# Sensors.net
KiCad netlist of a schematic drawn in Altium Designer
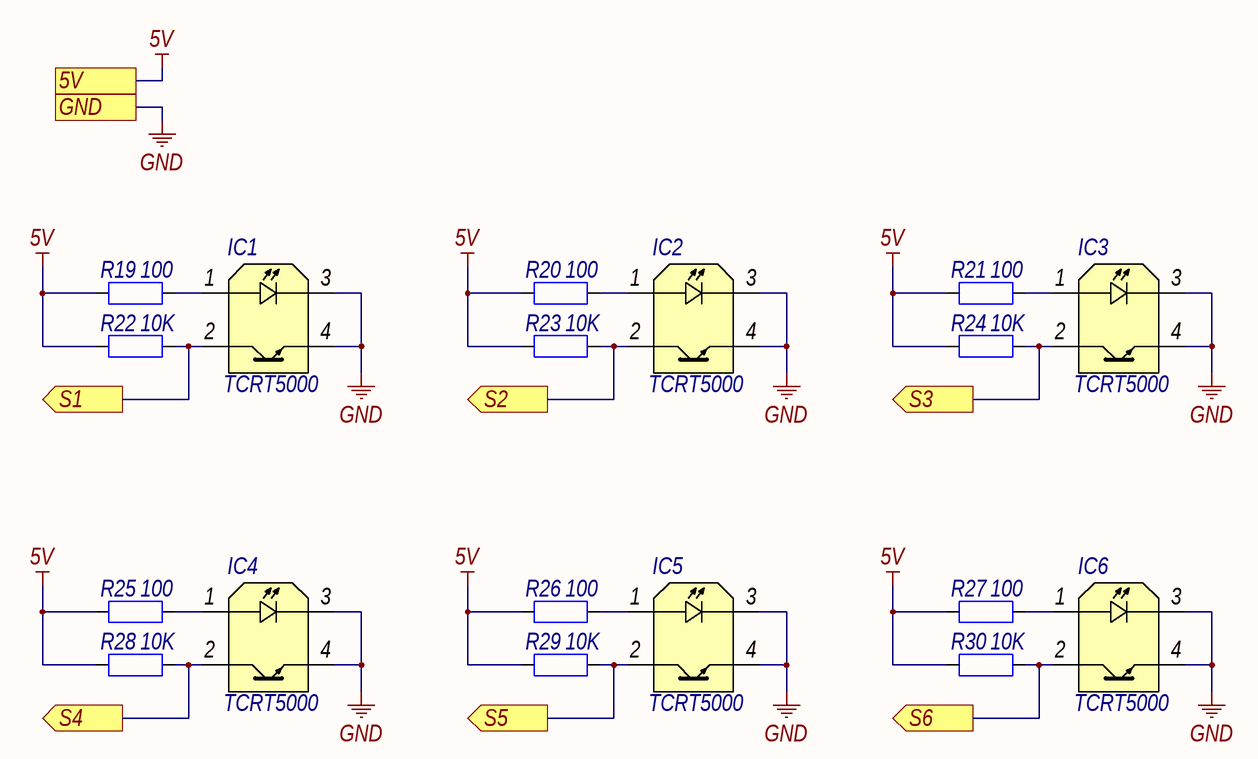
[diagram p0: Sensors.SchDoc]

(export (version "E")
  (design (tool "Eeschema 10.0.6"))
  (components
    (comp (ref "IC1")
      (value "TCRT5000")
      (footprint "Footprints:TCRT5000")
      (description "IR photointerrupter")
      (libsource (lib "Miscellaneous") (part "TCRT5000"))
    )
    (comp (ref "IC2")
      (value "TCRT5000")
      (footprint "Footprints:TCRT5000")
      (description "IR photointerrupter")
      (libsource (lib "Miscellaneous") (part "TCRT5000"))
    )
    (comp (ref "IC3")
      (value "TCRT5000")
      (footprint "Footprints:TCRT5000")
      (description "IR photointerrupter")
      (libsource (lib "Miscellaneous") (part "TCRT5000"))
    )
    (comp (ref "IC4")
      (value "TCRT5000")
      (footprint "Footprints:TCRT5000")
      (description "IR photointerrupter")
      (libsource (lib "Miscellaneous") (part "TCRT5000"))
    )
    (comp (ref "IC5")
      (value "TCRT5000")
      (footprint "Footprints:TCRT5000")
      (description "IR photointerrupter")
      (libsource (lib "Miscellaneous") (part "TCRT5000"))
    )
    (comp (ref "IC6")
      (value "TCRT5000")
      (footprint "Footprints:TCRT5000")
      (description "IR photointerrupter")
      (libsource (lib "Miscellaneous") (part "TCRT5000"))
    )
    (comp (ref "R19")
      (value "100")
      (footprint "Footprints:R0805")
      (description "Resistor")
      (libsource (lib "Passive") (part "Resistor"))
    )
    (comp (ref "R20")
      (value "100")
      (footprint "Footprints:R0805")
      (description "Resistor")
      (libsource (lib "Passive") (part "Resistor"))
    )
    (comp (ref "R21")
      (value "100")
      (footprint "Footprints:R0805")
      (description "Resistor")
      (libsource (lib "Passive") (part "Resistor"))
    )
    (comp (ref "R22")
      (value "10K")
      (footprint "Footprints:R0805")
      (description "Resistor")
      (libsource (lib "Passive") (part "Resistor"))
    )
    (comp (ref "R23")
      (value "10K")
      (footprint "Footprints:R0805")
      (description "Resistor")
      (libsource (lib "Passive") (part "Resistor"))
    )
    (comp (ref "R24")
      (value "10K")
      (footprint "Footprints:R0805")
      (description "Resistor")
      (libsource (lib "Passive") (part "Resistor"))
    )
    (comp (ref "R25")
      (value "100")
      (footprint "Footprints:R0805")
      (description "Resistor")
      (libsource (lib "Passive") (part "Resistor"))
    )
    (comp (ref "R26")
      (value "100")
      (footprint "Footprints:R0805")
      (description "Resistor")
      (libsource (lib "Passive") (part "Resistor"))
    )
    (comp (ref "R27")
      (value "100")
      (footprint "Footprints:R0805")
      (description "Resistor")
      (libsource (lib "Passive") (part "Resistor"))
    )
    (comp (ref "R28")
      (value "10K")
      (footprint "Footprints:R0805")
      (description "Resistor")
      (libsource (lib "Passive") (part "Resistor"))
    )
    (comp (ref "R29")
      (value "10K")
      (footprint "Footprints:R0805")
      (description "Resistor")
      (libsource (lib "Passive") (part "Resistor"))
    )
    (comp (ref "R30")
      (value "10K")
      (footprint "Footprints:R0805")
      (description "Resistor")
      (libsource (lib "Passive") (part "Resistor"))
    )
  )
  (nets
    (net (code "1") (name "/S1") (class "Default")
      (node (ref "IC1") (pin "2") (pinfunction "C_2") (pintype "passive"))
      (node (ref "R22") (pin "1") (pinfunction "1_1") (pintype "passive"))
    )
    (net (code "2") (name "/S2") (class "Default")
      (node (ref "IC2") (pin "2") (pinfunction "C_2") (pintype "passive"))
      (node (ref "R23") (pin "1") (pinfunction "1_1") (pintype "passive"))
    )
    (net (code "3") (name "/S3") (class "Default")
      (node (ref "IC3") (pin "2") (pinfunction "C_2") (pintype "passive"))
      (node (ref "R24") (pin "1") (pinfunction "1_1") (pintype "passive"))
    )
    (net (code "4") (name "/S4") (class "Default")
      (node (ref "IC4") (pin "2") (pinfunction "C_2") (pintype "passive"))
      (node (ref "R28") (pin "1") (pinfunction "1_1") (pintype "passive"))
    )
    (net (code "5") (name "/S5") (class "Default")
      (node (ref "IC5") (pin "2") (pinfunction "C_2") (pintype "passive"))
      (node (ref "R29") (pin "1") (pinfunction "1_1") (pintype "passive"))
    )
    (net (code "6") (name "/S6") (class "Default")
      (node (ref "IC6") (pin "2") (pinfunction "C_2") (pintype "passive"))
      (node (ref "R30") (pin "1") (pinfunction "1_1") (pintype "passive"))
    )
    (net (code "7") (name "5V") (class "Default")
      (node (ref "R19") (pin "2") (pinfunction "2_2") (pintype "passive"))
      (node (ref "R20") (pin "2") (pinfunction "2_2") (pintype "passive"))
      (node (ref "R21") (pin "2") (pinfunction "2_2") (pintype "passive"))
      (node (ref "R22") (pin "2") (pinfunction "2_2") (pintype "passive"))
      (node (ref "R23") (pin "2") (pinfunction "2_2") (pintype "passive"))
      (node (ref "R24") (pin "2") (pinfunction "2_2") (pintype "passive"))
      (node (ref "R25") (pin "2") (pinfunction "2_2") (pintype "passive"))
      (node (ref "R26") (pin "2") (pinfunction "2_2") (pintype "passive"))
      (node (ref "R27") (pin "2") (pinfunction "2_2") (pintype "passive"))
      (node (ref "R28") (pin "2") (pinfunction "2_2") (pintype "passive"))
      (node (ref "R29") (pin "2") (pinfunction "2_2") (pintype "passive"))
      (node (ref "R30") (pin "2") (pinfunction "2_2") (pintype "passive"))
    )
    (net (code "8") (name "GND") (class "Default")
      (node (ref "IC1") (pin "3") (pinfunction "C_3") (pintype "passive"))
      (node (ref "IC1") (pin "4") (pinfunction "E_4") (pintype "passive"))
      (node (ref "IC2") (pin "3") (pinfunction "C_3") (pintype "passive"))
      (node (ref "IC2") (pin "4") (pinfunction "E_4") (pintype "passive"))
      (node (ref "IC3") (pin "3") (pinfunction "C_3") (pintype "passive"))
      (node (ref "IC3") (pin "4") (pinfunction "E_4") (pintype "passive"))
      (node (ref "IC4") (pin "3") (pinfunction "C_3") (pintype "passive"))
      (node (ref "IC4") (pin "4") (pinfunction "E_4") (pintype "passive"))
      (node (ref "IC5") (pin "3") (pinfunction "C_3") (pintype "passive"))
      (node (ref "IC5") (pin "4") (pinfunction "E_4") (pintype "passive"))
      (node (ref "IC6") (pin "3") (pinfunction "C_3") (pintype "passive"))
      (node (ref "IC6") (pin "4") (pinfunction "E_4") (pintype "passive"))
    )
    (net (code "9") (name "Net-(IC1-A)") (class "Default")
      (node (ref "IC1") (pin "1") (pinfunction "A_1") (pintype "passive"))
      (node (ref "R19") (pin "1") (pinfunction "1_1") (pintype "passive"))
    )
    (net (code "10") (name "Net-(IC2-A)") (class "Default")
      (node (ref "IC2") (pin "1") (pinfunction "A_1") (pintype "passive"))
      (node (ref "R20") (pin "1") (pinfunction "1_1") (pintype "passive"))
    )
    (net (code "11") (name "Net-(IC3-A)") (class "Default")
      (node (ref "IC3") (pin "1") (pinfunction "A_1") (pintype "passive"))
      (node (ref "R21") (pin "1") (pinfunction "1_1") (pintype "passive"))
    )
    (net (code "12") (name "Net-(IC4-A)") (class "Default")
      (node (ref "IC4") (pin "1") (pinfunction "A_1") (pintype "passive"))
      (node (ref "R25") (pin "1") (pinfunction "1_1") (pintype "passive"))
    )
    (net (code "13") (name "Net-(IC5-A)") (class "Default")
      (node (ref "IC5") (pin "1") (pinfunction "A_1") (pintype "passive"))
      (node (ref "R26") (pin "1") (pinfunction "1_1") (pintype "passive"))
    )
    (net (code "14") (name "Net-(IC6-A)") (class "Default")
      (node (ref "IC6") (pin "1") (pinfunction "A_1") (pintype "passive"))
      (node (ref "R27") (pin "1") (pinfunction "1_1") (pintype "passive"))
    )
  )
)
